# simpleCH552_start.net
KiCad netlist of a schematic drawn in EAGLE
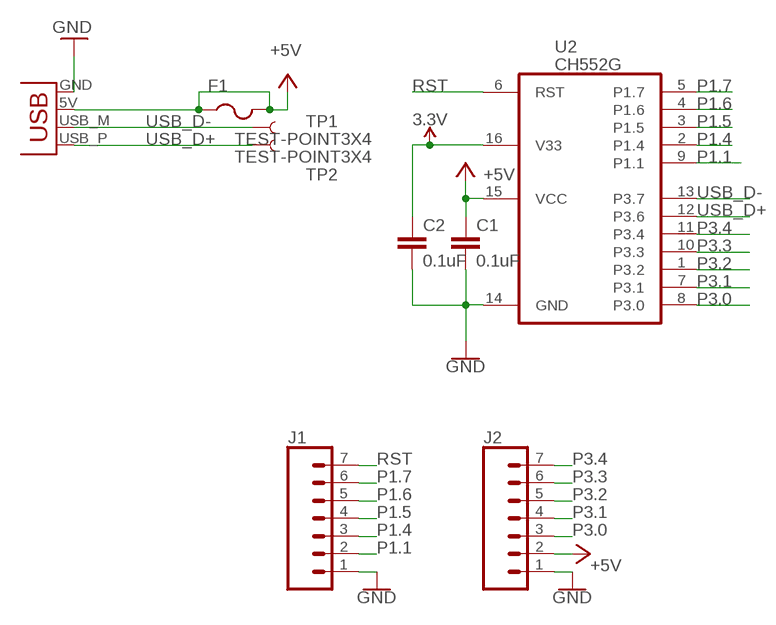
[diagram p0: schematic, sheet 1]

(export (version "E")
  (design (tool "Eeschema 10.0.6"))
  (components
    (comp (ref "C1")
      (value "0.1uF")
      (footprint "eagle-import:C0805K")
      (libsource (lib "eagle-import") (part "C-EUC0805K"))
    )
    (comp (ref "C2")
      (value "0.1uF")
      (footprint "eagle-import:C0805K")
      (libsource (lib "eagle-import") (part "C-EUC0805K"))
    )
    (comp (ref "F1")
      (value "PTCFUSE-1206")
      (footprint "eagle-import:R1206")
      (libsource (lib "eagle-import") (part "PTCFUSE-1206"))
    )
    (comp (ref "J1")
      (value "CONN_07NO_SILK")
      (footprint "eagle-import:1X07_NO_SILK")
      (libsource (lib "eagle-import") (part "CONN_07NO_SILK"))
    )
    (comp (ref "J2")
      (value "CONN_07NO_SILK")
      (footprint "eagle-import:1X07_NO_SILK")
      (libsource (lib "eagle-import") (part "CONN_07NO_SILK"))
    )
    (comp (ref "TP1")
      (value "TEST-POINT3X4")
      (footprint "eagle-import:PAD.03X.04")
      (libsource (lib "eagle-import") (part "TEST-POINT3X4"))
    )
    (comp (ref "TP2")
      (value "TEST-POINT3X4")
      (footprint "eagle-import:PAD.03X.04")
      (libsource (lib "eagle-import") (part "TEST-POINT3X4"))
    )
    (comp (ref "U2")
      (value "CH552G")
      (footprint "eagle-import:MY_IC_SO16")
      (libsource (lib "eagle-import") (part "MY_IC_CH551G_CH552GSOP-16"))
    )
    (comp (ref "X1")
      (value "USBPCB")
      (footprint "eagle-import:USB-A-PCB")
      (libsource (lib "eagle-import") (part "USBPCB"))
    )
  )
  (nets
    (net (code "1") (name "+5V") (class "Default")
      (node (ref "C1") (pin "1") (pinfunction "1_1") (pintype "passive"))
      (node (ref "F1") (pin "1") (pinfunction "1_1") (pintype "passive"))
      (node (ref "F1") (pin "2") (pinfunction "2_2") (pintype "passive"))
      (node (ref "J2") (pin "2") (pinfunction "2_2") (pintype "passive"))
      (node (ref "U2") (pin "15") (pinfunction "VCC_15") (pintype "power_in"))
      (node (ref "X1") (pin "5V") (pinfunction "VBUS_5V") (pintype "bidirectional"))
    )
    (net (code "2") (name "/P1.1") (class "Default")
      (node (ref "J1") (pin "2") (pinfunction "2_2") (pintype "passive"))
      (node (ref "U2") (pin "9") (pinfunction "P1.1_9") (pintype "bidirectional"))
    )
    (net (code "3") (name "/P1.4") (class "Default")
      (node (ref "J1") (pin "3") (pinfunction "3_3") (pintype "passive"))
      (node (ref "U2") (pin "2") (pinfunction "P1.4_2") (pintype "bidirectional"))
    )
    (net (code "4") (name "/P1.5") (class "Default")
      (node (ref "J1") (pin "4") (pinfunction "4_4") (pintype "passive"))
      (node (ref "U2") (pin "3") (pinfunction "P1.5_3") (pintype "bidirectional"))
    )
    (net (code "5") (name "/P1.6") (class "Default")
      (node (ref "J1") (pin "5") (pinfunction "5_5") (pintype "passive"))
      (node (ref "U2") (pin "4") (pinfunction "P1.6_4") (pintype "bidirectional"))
    )
    (net (code "6") (name "/P1.7") (class "Default")
      (node (ref "J1") (pin "6") (pinfunction "6_6") (pintype "passive"))
      (node (ref "U2") (pin "5") (pinfunction "P1.7_5") (pintype "bidirectional"))
    )
    (net (code "7") (name "/P3.0") (class "Default")
      (node (ref "J2") (pin "3") (pinfunction "3_3") (pintype "passive"))
      (node (ref "U2") (pin "8") (pinfunction "P3.0_8") (pintype "bidirectional"))
    )
    (net (code "8") (name "/P3.1") (class "Default")
      (node (ref "J2") (pin "4") (pinfunction "4_4") (pintype "passive"))
      (node (ref "U2") (pin "7") (pinfunction "P3.1_7") (pintype "bidirectional"))
    )
    (net (code "9") (name "/P3.2") (class "Default")
      (node (ref "J2") (pin "5") (pinfunction "5_5") (pintype "passive"))
      (node (ref "U2") (pin "1") (pinfunction "P3.2_1") (pintype "bidirectional"))
    )
    (net (code "10") (name "/P3.3") (class "Default")
      (node (ref "J2") (pin "6") (pinfunction "6_6") (pintype "passive"))
      (node (ref "U2") (pin "10") (pinfunction "P3.3_10") (pintype "bidirectional"))
    )
    (net (code "11") (name "/P3.4") (class "Default")
      (node (ref "J2") (pin "7") (pinfunction "7_7") (pintype "passive"))
      (node (ref "U2") (pin "11") (pinfunction "P3.4_11") (pintype "bidirectional"))
    )
    (net (code "12") (name "/RST") (class "Default")
      (node (ref "J1") (pin "7") (pinfunction "7_7") (pintype "passive"))
      (node (ref "U2") (pin "6") (pinfunction "RST_6") (pintype "input"))
    )
    (net (code "13") (name "/USB_D+") (class "Default")
      (node (ref "TP2") (pin "P$1") (pinfunction "1_P$1") (pintype "bidirectional"))
      (node (ref "U2") (pin "12") (pinfunction "P3.6_12") (pintype "bidirectional"))
      (node (ref "X1") (pin "USB_P") (pinfunction "D+_USB_P") (pintype "bidirectional"))
    )
    (net (code "14") (name "/USB_D-") (class "Default")
      (node (ref "TP1") (pin "P$1") (pinfunction "1_P$1") (pintype "bidirectional"))
      (node (ref "U2") (pin "13") (pinfunction "P3.7_13") (pintype "bidirectional"))
      (node (ref "X1") (pin "USB_M") (pinfunction "D-_USB_M") (pintype "bidirectional"))
    )
    (net (code "15") (name "3.3V") (class "Default")
      (node (ref "C2") (pin "1") (pinfunction "1_1") (pintype "passive"))
      (node (ref "U2") (pin "16") (pinfunction "V33_16") (pintype "power_in"))
    )
    (net (code "16") (name "GND") (class "Default")
      (node (ref "C1") (pin "2") (pinfunction "2_2") (pintype "passive"))
      (node (ref "C2") (pin "2") (pinfunction "2_2") (pintype "passive"))
      (node (ref "J1") (pin "1") (pinfunction "1_1") (pintype "passive"))
      (node (ref "J2") (pin "1") (pinfunction "1_1") (pintype "passive"))
      (node (ref "U2") (pin "14") (pinfunction "GND_14") (pintype "power_in"))
      (node (ref "X1") (pin "GND") (pinfunction "GND_GND") (pintype "bidirectional"))
    )
  )
)
